# circuitPendulum4TIA00.net
KiCad netlist of a schematic drawn in EAGLE
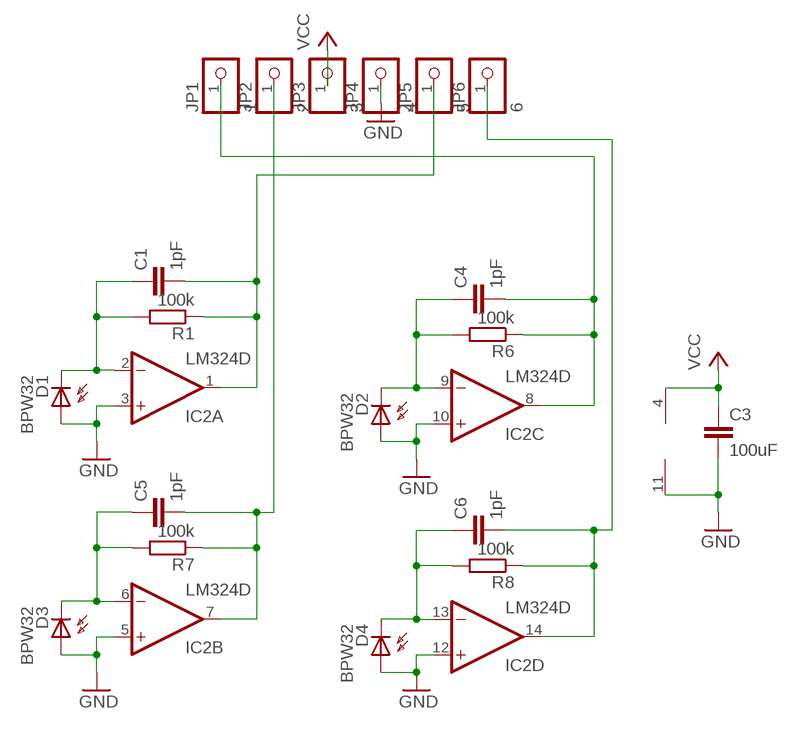
[diagram p0: schematic, sheet 1]

(export (version "E")
  (design (tool "Eeschema 10.0.6"))
  (components
    (comp (ref "C1")
      (value "1pF")
      (footprint "eagle-import:C0603")
      (libsource (lib "eagle-import") (part "C-EUC0603"))
    )
    (comp (ref "C3")
      (value "100uF")
      (footprint "eagle-import:C0603")
      (libsource (lib "eagle-import") (part "C-EUC0603"))
    )
    (comp (ref "C4")
      (value "1pF")
      (footprint "eagle-import:C0603")
      (libsource (lib "eagle-import") (part "C-EUC0603"))
    )
    (comp (ref "C5")
      (value "1pF")
      (footprint "eagle-import:C0603")
      (libsource (lib "eagle-import") (part "C-EUC0603"))
    )
    (comp (ref "C6")
      (value "1pF")
      (footprint "eagle-import:C0603")
      (libsource (lib "eagle-import") (part "C-EUC0603"))
    )
    (comp (ref "D1")
      (value "BPW32")
      (footprint "eagle-import:BPW32")
      (libsource (lib "eagle-import") (part "BPW32"))
    )
    (comp (ref "D2")
      (value "BPW32")
      (footprint "eagle-import:BPW32")
      (libsource (lib "eagle-import") (part "BPW32"))
    )
    (comp (ref "D3")
      (value "BPW32")
      (footprint "eagle-import:BPW32")
      (libsource (lib "eagle-import") (part "BPW32"))
    )
    (comp (ref "D4")
      (value "BPW32")
      (footprint "eagle-import:BPW32")
      (libsource (lib "eagle-import") (part "BPW32"))
    )
    (comp (ref "IC2")
      (value "LM324D")
      (footprint "eagle-import:SO14")
      (libsource (lib "eagle-import") (part "LM324D"))
    )
    (comp (ref "JP1")
      (value "1")
      (footprint "eagle-import:1X01SMD")
      (libsource (lib "eagle-import") (part "PINHD-1X1_2.54-SMD"))
    )
    (comp (ref "JP2")
      (value "2")
      (footprint "eagle-import:1X01SMD")
      (libsource (lib "eagle-import") (part "PINHD-1X1_2.54-SMD"))
    )
    (comp (ref "JP3")
      (value "3")
      (footprint "eagle-import:1X01SMD")
      (libsource (lib "eagle-import") (part "PINHD-1X1_2.54-SMD"))
    )
    (comp (ref "JP4")
      (value "4")
      (footprint "eagle-import:1X01SMD")
      (libsource (lib "eagle-import") (part "PINHD-1X1_2.54-SMD"))
    )
    (comp (ref "JP5")
      (value "5")
      (footprint "eagle-import:1X01SMD")
      (libsource (lib "eagle-import") (part "PINHD-1X1_2.54-SMD"))
    )
    (comp (ref "JP6")
      (value "6")
      (footprint "eagle-import:1X01SMD")
      (libsource (lib "eagle-import") (part "PINHD-1X1_2.54-SMD"))
    )
    (comp (ref "R1")
      (value "100k")
      (footprint "eagle-import:R0603")
      (libsource (lib "eagle-import") (part "R-EU_R0603"))
    )
    (comp (ref "R6")
      (value "100k")
      (footprint "eagle-import:R0603")
      (libsource (lib "eagle-import") (part "R-EU_R0603"))
    )
    (comp (ref "R7")
      (value "100k")
      (footprint "eagle-import:R0603")
      (libsource (lib "eagle-import") (part "R-EU_R0603"))
    )
    (comp (ref "R8")
      (value "100k")
      (footprint "eagle-import:R0603")
      (libsource (lib "eagle-import") (part "R-EU_R0603"))
    )
  )
  (nets
    (net (code "1") (name "GND") (class "Default")
      (node (ref "C3") (pin "2") (pinfunction "2_2") (pintype "passive"))
      (node (ref "D1") (pin "A") (pinfunction "A_A") (pintype "passive"))
      (node (ref "D2") (pin "A") (pinfunction "A_A") (pintype "passive"))
      (node (ref "D3") (pin "A") (pinfunction "A_A") (pintype "passive"))
      (node (ref "D4") (pin "A") (pinfunction "A_A") (pintype "passive"))
      (node (ref "IC2") (pin "10") (pinfunction "+IN_10") (pintype "input"))
      (node (ref "IC2") (pin "11") (pinfunction "V-_11") (pintype "power_in"))
      (node (ref "IC2") (pin "12") (pinfunction "+IN_12") (pintype "input"))
      (node (ref "IC2") (pin "3") (pinfunction "+IN_3") (pintype "input"))
      (node (ref "IC2") (pin "5") (pinfunction "+IN_5") (pintype "input"))
      (node (ref "JP4") (pin "1") (pinfunction "1_1") (pintype "passive"))
    )
    (net (code "2") (name "Net-(D1-C)") (class "Default")
      (node (ref "C1") (pin "1") (pinfunction "1_1") (pintype "passive"))
      (node (ref "D1") (pin "K") (pinfunction "C_K") (pintype "passive"))
      (node (ref "IC2") (pin "2") (pinfunction "-IN_2") (pintype "input"))
      (node (ref "R1") (pin "2") (pinfunction "2_2") (pintype "passive"))
    )
    (net (code "3") (name "Net-(D2-C)") (class "Default")
      (node (ref "C4") (pin "1") (pinfunction "1_1") (pintype "passive"))
      (node (ref "D2") (pin "K") (pinfunction "C_K") (pintype "passive"))
      (node (ref "IC2") (pin "9") (pinfunction "-IN_9") (pintype "input"))
      (node (ref "R6") (pin "2") (pinfunction "2_2") (pintype "passive"))
    )
    (net (code "4") (name "Net-(D3-C)") (class "Default")
      (node (ref "C5") (pin "1") (pinfunction "1_1") (pintype "passive"))
      (node (ref "D3") (pin "K") (pinfunction "C_K") (pintype "passive"))
      (node (ref "IC2") (pin "6") (pinfunction "-IN_6") (pintype "input"))
      (node (ref "R7") (pin "2") (pinfunction "2_2") (pintype "passive"))
    )
    (net (code "5") (name "Net-(D4-C)") (class "Default")
      (node (ref "C6") (pin "1") (pinfunction "1_1") (pintype "passive"))
      (node (ref "D4") (pin "K") (pinfunction "C_K") (pintype "passive"))
      (node (ref "IC2") (pin "13") (pinfunction "-IN_13") (pintype "input"))
      (node (ref "R8") (pin "2") (pinfunction "2_2") (pintype "passive"))
    )
    (net (code "6") (name "Net-(IC2A-OUT)") (class "Default")
      (node (ref "C1") (pin "2") (pinfunction "2_2") (pintype "passive"))
      (node (ref "IC2") (pin "1") (pinfunction "OUT_1") (pintype "output"))
      (node (ref "JP5") (pin "1") (pinfunction "1_1") (pintype "passive"))
      (node (ref "R1") (pin "1") (pinfunction "1_1") (pintype "passive"))
    )
    (net (code "7") (name "Net-(IC2B-OUT)") (class "Default")
      (node (ref "C5") (pin "2") (pinfunction "2_2") (pintype "passive"))
      (node (ref "IC2") (pin "7") (pinfunction "OUT_7") (pintype "output"))
      (node (ref "JP2") (pin "1") (pinfunction "1_1") (pintype "passive"))
      (node (ref "R7") (pin "1") (pinfunction "1_1") (pintype "passive"))
    )
    (net (code "8") (name "Net-(IC2C-OUT)") (class "Default")
      (node (ref "C4") (pin "2") (pinfunction "2_2") (pintype "passive"))
      (node (ref "IC2") (pin "8") (pinfunction "OUT_8") (pintype "output"))
      (node (ref "JP1") (pin "1") (pinfunction "1_1") (pintype "passive"))
      (node (ref "R6") (pin "1") (pinfunction "1_1") (pintype "passive"))
    )
    (net (code "9") (name "Net-(IC2D-OUT)") (class "Default")
      (node (ref "C6") (pin "2") (pinfunction "2_2") (pintype "passive"))
      (node (ref "IC2") (pin "14") (pinfunction "OUT_14") (pintype "output"))
      (node (ref "JP6") (pin "1") (pinfunction "1_1") (pintype "passive"))
      (node (ref "R8") (pin "1") (pinfunction "1_1") (pintype "passive"))
    )
    (net (code "10") (name "VCC") (class "Default")
      (node (ref "C3") (pin "1") (pinfunction "1_1") (pintype "passive"))
      (node (ref "IC2") (pin "4") (pinfunction "V+_4") (pintype "power_in"))
      (node (ref "JP3") (pin "1") (pinfunction "1_1") (pintype "passive"))
    )
  )
)
